# humidity.net
KiCad netlist of a schematic drawn in Altium Designer
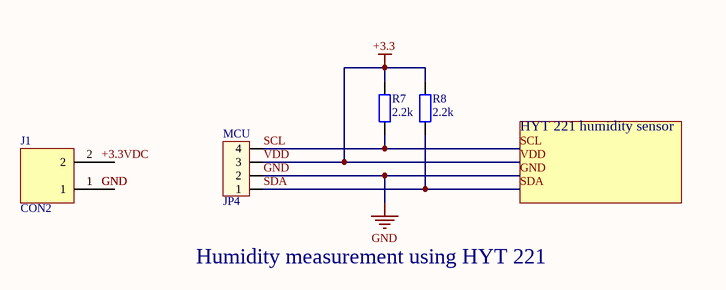
[diagram p0: humidity.SchDoc]

(export (version "E")
  (design (tool "Eeschema 10.0.6"))
  (components
    (comp (ref "J1") (value "CON2") (footprint "HEDH") (libsource (lib "syhaunguyen") (part "CON2_1")))
    (comp (ref "MCU")
      (value "JP4")
      (footprint "CON4")
      (description "Connector 4")
      (libsource (lib "syhaunguyen") (part "Con4"))
    )
    (comp (ref "R7")
      (value "2.2k")
      (footprint "R1/4W")
      (description "Resistor 1/4W")
      (libsource (lib "syhaunguyen") (part "R1/4W"))
    )
    (comp (ref "R8")
      (value "2.2k")
      (footprint "R1/4W")
      (description "Resistor 1/4W")
      (libsource (lib "syhaunguyen") (part "R1/4W"))
    )
  )
  (nets
    (net (code "1") (name "+3.3") (class "Default")
      (node (ref "MCU") (pin "3") (pinfunction "3_3") (pintype "passive"))
      (node (ref "R7") (pin "2") (pinfunction "2_2") (pintype "passive"))
      (node (ref "R8") (pin "2") (pinfunction "2_2") (pintype "passive"))
    )
    (net (code "3") (name "/SCL") (class "Default")
      (node (ref "MCU") (pin "4") (pinfunction "4_4") (pintype "passive"))
      (node (ref "R7") (pin "1") (pinfunction "1_1") (pintype "passive"))
    )
    (net (code "4") (name "/SDA") (class "Default")
      (node (ref "MCU") (pin "1") (pinfunction "1_1") (pintype "passive"))
      (node (ref "R8") (pin "1") (pinfunction "1_1") (pintype "passive"))
    )
    (net (code "5") (name "GND") (class "Default")
      (node (ref "MCU") (pin "2") (pinfunction "2_2") (pintype "passive"))
    )
    (net (code "6") (name "unconnected-(J1-Pad1)") (class "Default")
      (node (ref "J1") (pin "1") (pinfunction "1_1") (pintype "passive"))
    )
    (net (code "7") (name "unconnected-(J1-Pad2)") (class "Default")
      (node (ref "J1") (pin "2") (pinfunction "2_2") (pintype "passive"))
    )
  )
)
